# T962a_Panel.net
KiCad netlist of a schematic drawn in Altium Designer
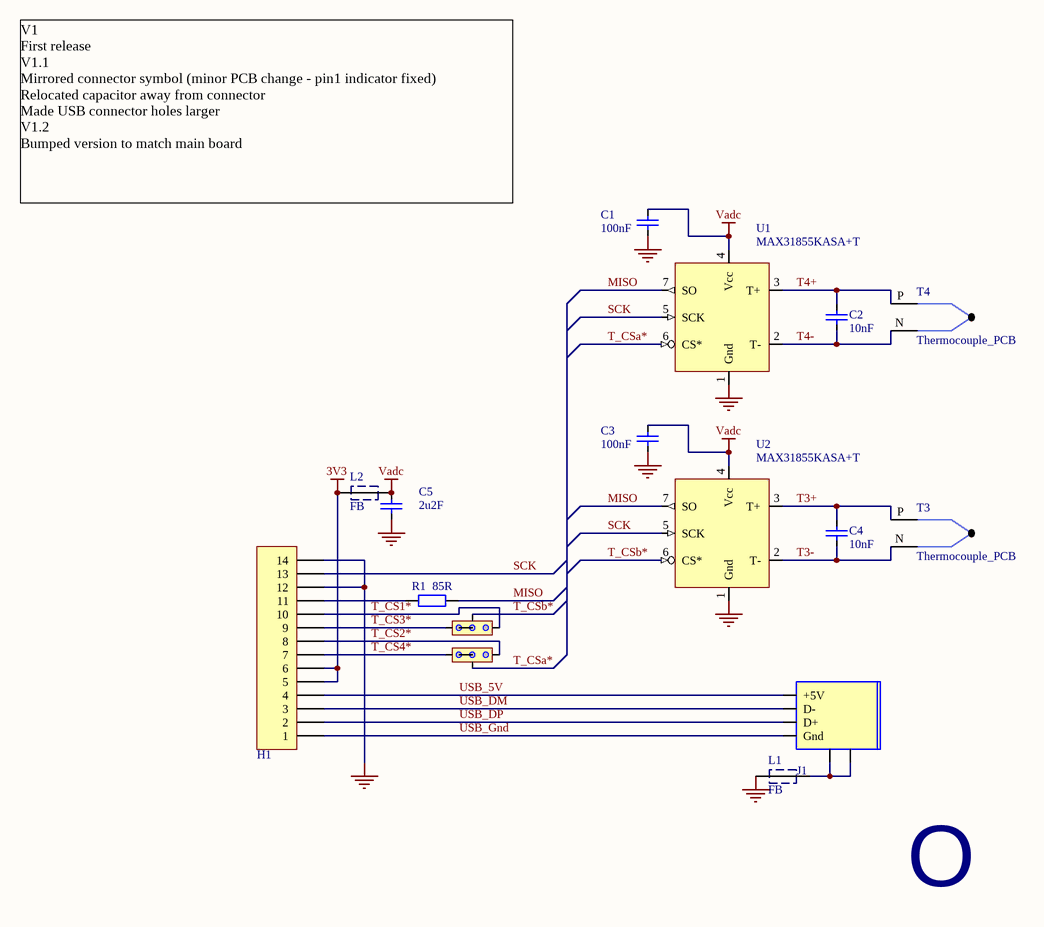
[diagram p0: T962a_Panel.SchDoc]

(export (version "E")
  (design (tool "Eeschema 10.0.6"))
  (components
    (comp (ref "C1")
      (value "100nF")
      (footprint "CCNP1608-0603")
      (description "Capacitor")
      (fields
        (field (name "MANUFACTURER") "Generic Components")
        (field (name "PUBLISHER") "Altium Hobart Technology Centre")
      )
      (libsource (lib "MyLibrary") (part "Cap"))
    )
    (comp (ref "C2")
      (value "10nF")
      (footprint "CCNP1608-0603")
      (description "Capacitor")
      (fields
        (field (name "MANUFACTURER") "Generic Components")
        (field (name "PUBLISHER") "Altium Hobart Technology Centre")
      )
      (libsource (lib "MyLibrary") (part "Cap"))
    )
    (comp (ref "C3")
      (value "100nF")
      (footprint "CCNP1608-0603")
      (description "Capacitor")
      (fields
        (field (name "MANUFACTURER") "Generic Components")
        (field (name "PUBLISHER") "Altium Hobart Technology Centre")
      )
      (libsource (lib "MyLibrary") (part "Cap"))
    )
    (comp (ref "C4")
      (value "10nF")
      (footprint "CCNP1608-0603")
      (description "Capacitor")
      (fields
        (field (name "MANUFACTURER") "Generic Components")
        (field (name "PUBLISHER") "Altium Hobart Technology Centre")
      )
      (libsource (lib "MyLibrary") (part "Cap"))
    )
    (comp (ref "C5")
      (value "2u2F")
      (footprint "CCNP2012-0805")
      (description "Capacitor")
      (fields
        (field (name "MANUFACTURER") "Generic Components")
        (field (name "PUBLISHER") "Altium Hobart Technology Centre")
      )
      (libsource (lib "MyLibrary") (part "Cap"))
    )
    (comp (ref "H1")
      (value "2x5 Header")
      (footprint "HDR2X7S")
      (description "Header 2x7")
      (libsource (lib "MyLibrary") (part "Header 2x7"))
    )
    (comp (ref "J1")
      (value "USB Type B")
      (footprint "USB_BCon - straight pins")
      (description "USB B Connector")
      (libsource (lib "MyLibrary") (part "USB_TYPE_B"))
    )
    (comp (ref "L1")
      (value "FB")
      (footprint "CR2012-0805")
      (description "Ferrite Bead (0805) 0.045OHM, 2A")
      (libsource (lib "MyLibrary") (part "Ferrite Bead 0805"))
    )
    (comp (ref "L2")
      (value "FB")
      (footprint "CR2012-0805")
      (description "Ferrite Bead (0805) 0.045OHM, 2A")
      (libsource (lib "MyLibrary") (part "Ferrite Bead 0805"))
    )
    (comp (ref "Logo")
      (value "OSHW Logo")
      (footprint "OSHW")
      (libsource (lib "MyLibrary") (part "OSHW Logo"))
    )
    (comp (ref "R1")
      (value "85R")
      (footprint "CR2012-0805")
      (description "Resistor")
      (fields
        (field (name "MANUFACTURER") "Generic Components")
        (field (name "PUBLISHER") "Altium Hobart Technology Centre")
      )
      (libsource (lib "MyLibrary") (part "Res"))
    )
    (comp (ref "S1")
      (value "Link3Closed")
      (footprint "SolderBridge3(Closed)")
      (libsource (lib "") (part "Link3Closed_1"))
    )
    (comp (ref "S2")
      (value "Link3Closed")
      (footprint "SolderBridge3(Closed)")
      (libsource (lib "MyLibrary") (part "Link3Closed"))
    )
    (comp (ref "T3")
      (value "Thermocouple_PCB")
      (footprint "ThermoCoupleSocket - PCB mount")
      (libsource (lib "MySchLib") (part "Thermocouple_PCB"))
    )
    (comp (ref "T4")
      (value "Thermocouple_PCB")
      (footprint "ThermoCoupleSocket - PCB mount")
      (libsource (lib "MySchLib") (part "Thermocouple_PCB"))
    )
    (comp (ref "U1")
      (value "MAX31855KASA+T")
      (footprint "SO-8_L")
      (libsource (lib "MySchLib") (part "MAX31855KASA+T"))
    )
    (comp (ref "U2")
      (value "MAX31855KASA+T")
      (footprint "SO-8_L")
      (libsource (lib "MySchLib") (part "MAX31855KASA+T"))
    )
  )
  (nets
    (net (code "1") (name "/MISO") (class "Default")
      (node (ref "R1") (pin "2") (pinfunction "2_2") (pintype "passive"))
      (node (ref "U1") (pin "7") (pinfunction "SO_7") (pintype "output"))
      (node (ref "U2") (pin "7") (pinfunction "SO_7") (pintype "output"))
    )
    (net (code "2") (name "/SCK") (class "Default")
      (node (ref "H1") (pin "13") (pinfunction "13_13") (pintype "passive"))
      (node (ref "U1") (pin "5") (pinfunction "SCK_5") (pintype "input"))
      (node (ref "U2") (pin "5") (pinfunction "SCK_5") (pintype "input"))
    )
    (net (code "3") (name "/T3+") (class "Default")
      (node (ref "C4") (pin "1") (pinfunction "1_1") (pintype "passive"))
      (node (ref "T3") (pin "P") (pinfunction "P_P") (pintype "passive"))
      (node (ref "U2") (pin "3") (pinfunction "T+_3") (pintype "passive"))
    )
    (net (code "4") (name "/T3-") (class "Default")
      (node (ref "C4") (pin "2") (pinfunction "2_2") (pintype "passive"))
      (node (ref "T3") (pin "N") (pinfunction "N_N") (pintype "passive"))
      (node (ref "U2") (pin "2") (pinfunction "T-_2") (pintype "passive"))
    )
    (net (code "5") (name "/T4+") (class "Default")
      (node (ref "C2") (pin "1") (pinfunction "1_1") (pintype "passive"))
      (node (ref "T4") (pin "P") (pinfunction "P_P") (pintype "passive"))
      (node (ref "U1") (pin "3") (pinfunction "T+_3") (pintype "passive"))
    )
    (net (code "6") (name "/T4-") (class "Default")
      (node (ref "C2") (pin "2") (pinfunction "2_2") (pintype "passive"))
      (node (ref "T4") (pin "N") (pinfunction "N_N") (pintype "passive"))
      (node (ref "U1") (pin "2") (pinfunction "T-_2") (pintype "passive"))
    )
    (net (code "7") (name "/T_CS1*") (class "Default")
      (node (ref "H1") (pin "10") (pinfunction "10_10") (pintype "passive"))
      (node (ref "S1") (pin "3") (pintype "passive"))
    )
    (net (code "8") (name "/T_CS2*") (class "Default")
      (node (ref "H1") (pin "8") (pinfunction "8_8") (pintype "passive"))
      (node (ref "S2") (pin "3") (pintype "passive"))
    )
    (net (code "9") (name "/T_CS3*") (class "Default")
      (node (ref "H1") (pin "9") (pinfunction "9_9") (pintype "passive"))
      (node (ref "S1") (pin "1") (pintype "passive"))
    )
    (net (code "10") (name "/T_CS4*") (class "Default")
      (node (ref "H1") (pin "7") (pinfunction "7_7") (pintype "passive"))
      (node (ref "S2") (pin "1") (pintype "passive"))
    )
    (net (code "11") (name "/T_CSa*") (class "Default")
      (node (ref "S2") (pin "2") (pintype "passive"))
      (node (ref "U1") (pin "6") (pinfunction "CS*_6") (pintype "input"))
    )
    (net (code "12") (name "/T_CSb*") (class "Default")
      (node (ref "S1") (pin "2") (pintype "passive"))
      (node (ref "U2") (pin "6") (pinfunction "CS*_6") (pintype "input"))
    )
    (net (code "13") (name "/USB_5V") (class "Default")
      (node (ref "H1") (pin "4") (pinfunction "4_4") (pintype "passive"))
      (node (ref "J1") (pin "5V") (pinfunction "+5V_5V") (pintype "power_in"))
    )
    (net (code "14") (name "/USB_DM") (class "Default")
      (node (ref "H1") (pin "3") (pinfunction "3_3") (pintype "passive"))
      (node (ref "J1") (pin "D-") (pinfunction "D-_D-") (pintype "passive"))
    )
    (net (code "15") (name "/USB_DP") (class "Default")
      (node (ref "H1") (pin "2") (pinfunction "2_2") (pintype "passive"))
      (node (ref "J1") (pin "D+") (pinfunction "D+_D+") (pintype "passive"))
    )
    (net (code "16") (name "/USB_Gnd") (class "Default")
      (node (ref "H1") (pin "1") (pinfunction "1_1") (pintype "passive"))
      (node (ref "J1") (pin "Gnd") (pinfunction "Gnd_Gnd") (pintype "passive"))
    )
    (net (code "17") (name "3V3") (class "Default")
      (node (ref "H1") (pin "5") (pinfunction "5_5") (pintype "passive"))
      (node (ref "H1") (pin "6") (pinfunction "6_6") (pintype "passive"))
      (node (ref "L2") (pin "1") (pinfunction "1_1") (pintype "passive"))
    )
    (net (code "18") (name "GND") (class "Default")
      (node (ref "C1") (pin "1") (pinfunction "1_1") (pintype "passive"))
      (node (ref "C3") (pin "1") (pinfunction "1_1") (pintype "passive"))
      (node (ref "C5") (pin "1") (pinfunction "1_1") (pintype "passive"))
      (node (ref "H1") (pin "12") (pinfunction "12_12") (pintype "passive"))
      (node (ref "H1") (pin "14") (pinfunction "14_14") (pintype "passive"))
      (node (ref "L1") (pin "1") (pinfunction "1_1") (pintype "passive"))
      (node (ref "U1") (pin "1") (pinfunction "Gnd_1") (pintype "power_in"))
      (node (ref "U2") (pin "1") (pinfunction "Gnd_1") (pintype "power_in"))
    )
    (net (code "19") (name "Net-(H1-Pad11)") (class "Default")
      (node (ref "H1") (pin "11") (pinfunction "11_11") (pintype "passive"))
      (node (ref "R1") (pin "1") (pinfunction "1_1") (pintype "passive"))
    )
    (net (code "20") (name "Net-(J1-USBShd-PadShield1)") (class "Default")
      (node (ref "J1") (pin "Shield1") (pinfunction "USBShd_Shield1") (pintype "passive"))
      (node (ref "J1") (pin "Shield2") (pinfunction "USBShd_Shield2") (pintype "passive"))
      (node (ref "L1") (pin "2") (pinfunction "2_2") (pintype "passive"))
    )
    (net (code "21") (name "Vadc") (class "Default")
      (node (ref "C1") (pin "2") (pinfunction "2_2") (pintype "passive"))
      (node (ref "C3") (pin "2") (pinfunction "2_2") (pintype "passive"))
      (node (ref "C5") (pin "2") (pinfunction "2_2") (pintype "passive"))
      (node (ref "L2") (pin "2") (pinfunction "2_2") (pintype "passive"))
      (node (ref "U1") (pin "4") (pinfunction "Vcc_4") (pintype "power_in"))
      (node (ref "U2") (pin "4") (pinfunction "Vcc_4") (pintype "power_in"))
    )
    (net (code "22") (name "unconnected-(U1-NC-Pad8)") (class "Default")
      (node (ref "U1") (pin "8") (pinfunction "NC_8") (pintype "passive"))
    )
    (net (code "23") (name "unconnected-(U2-NC-Pad8)") (class "Default")
      (node (ref "U2") (pin "8") (pinfunction "NC_8") (pintype "passive"))
    )
  )
)
